# RGBledMiniStick.net
KiCad netlist of a schematic drawn in EAGLE
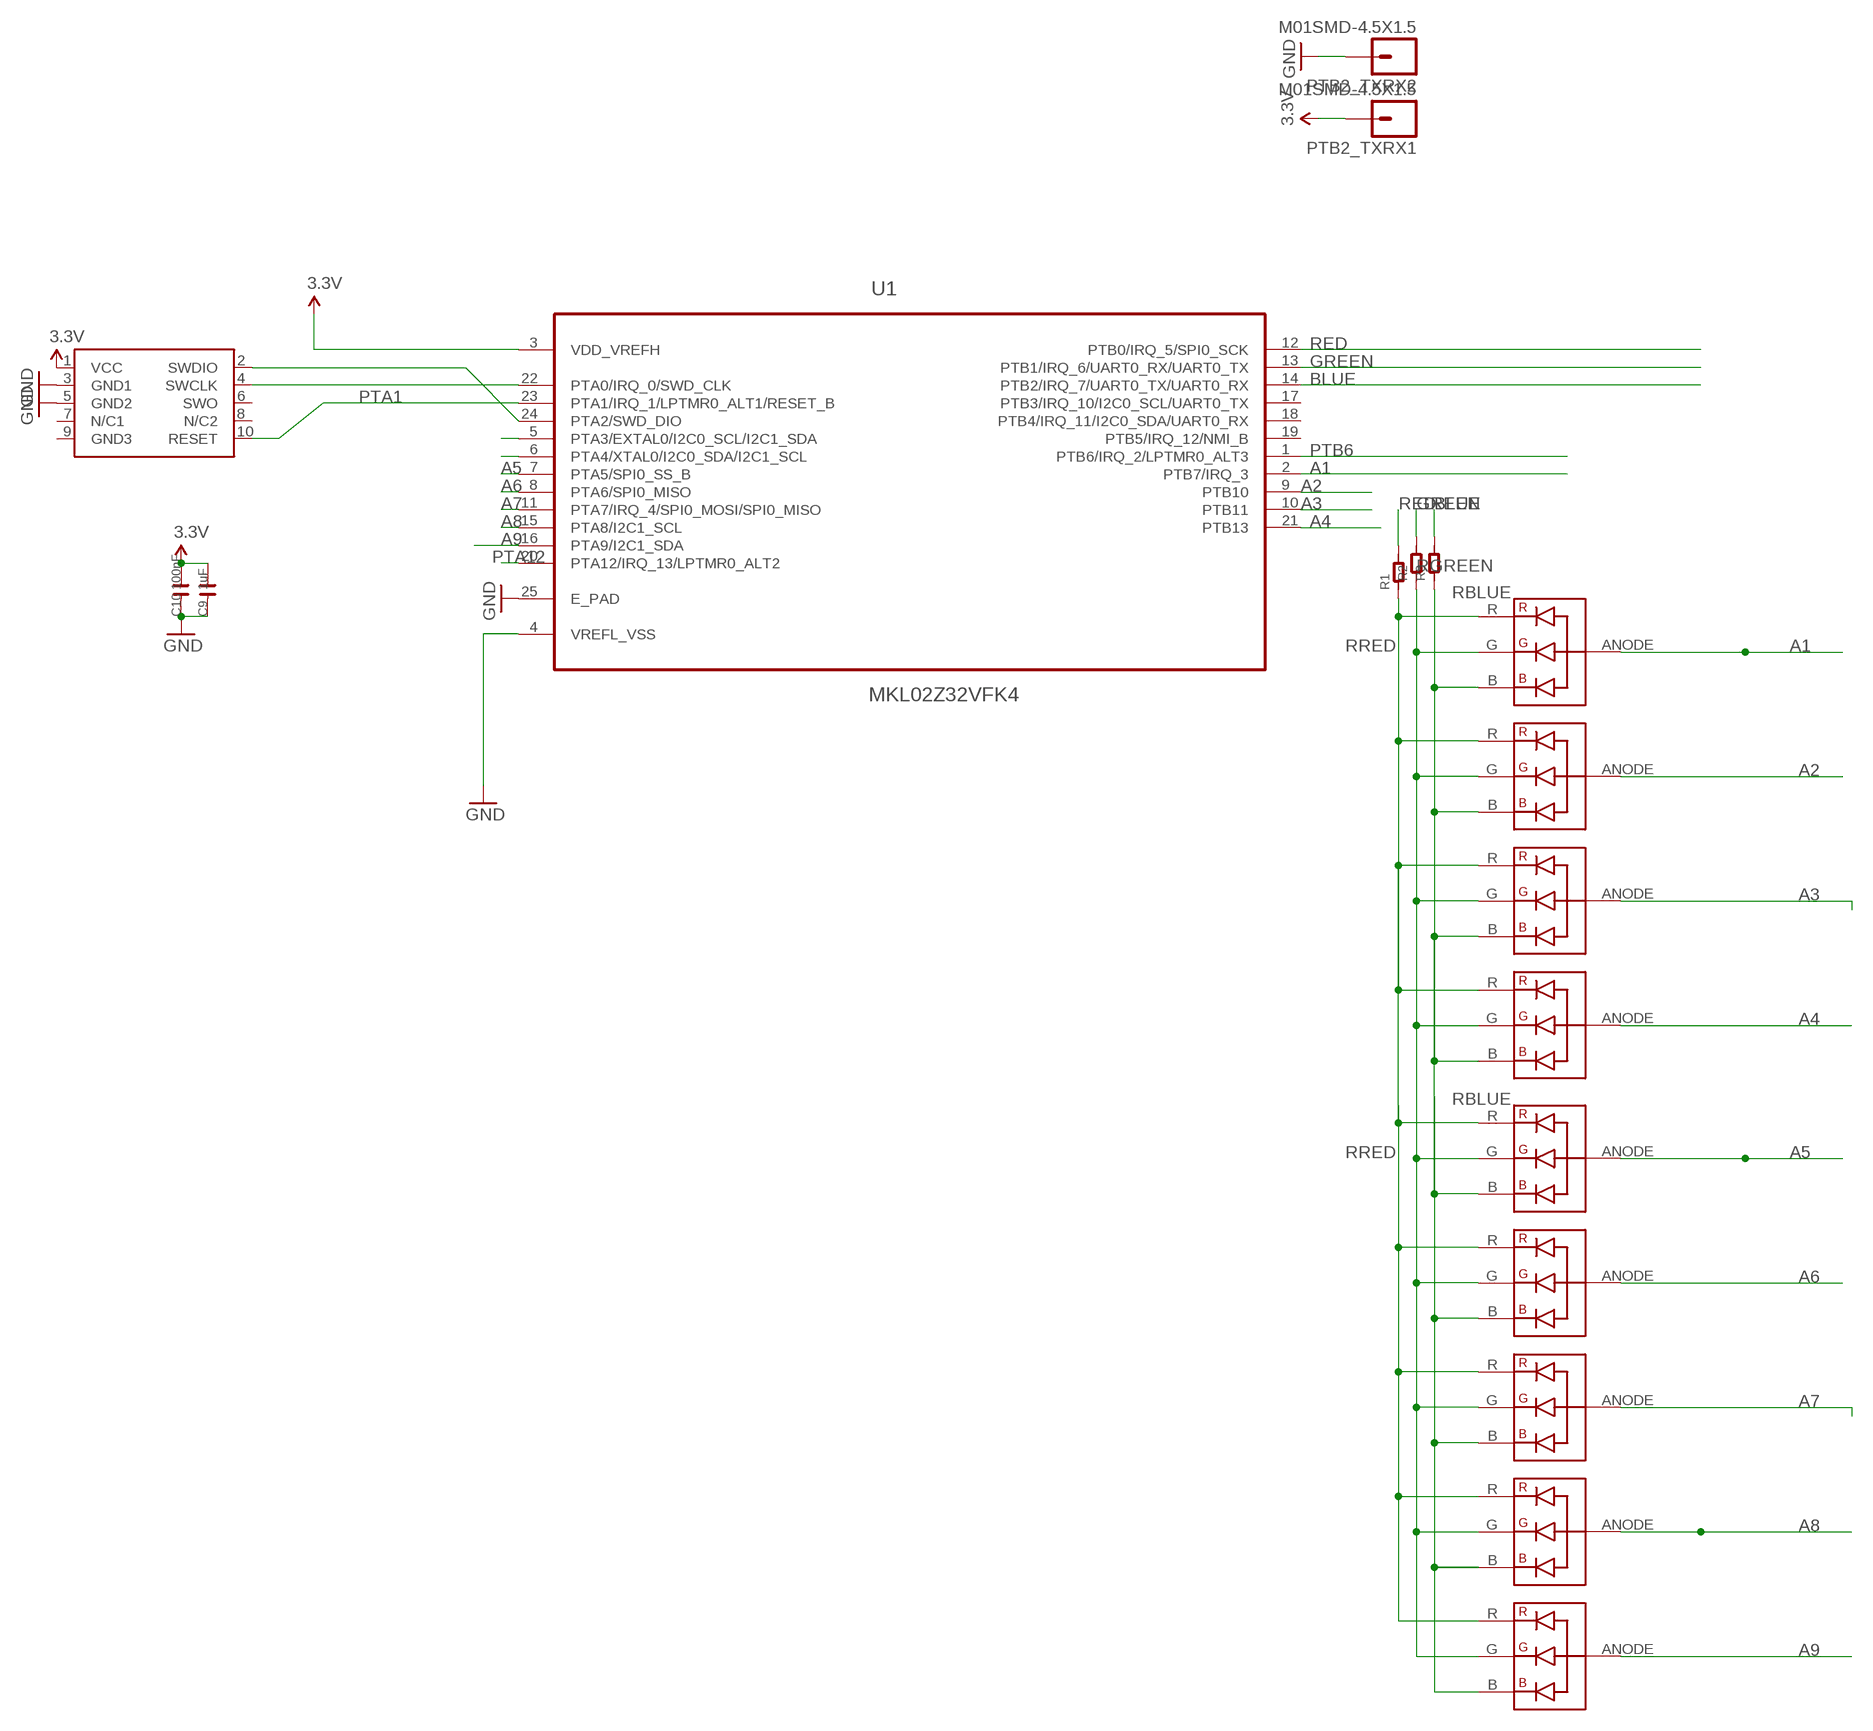
[diagram p0: schematic, sheet 1]

(export (version "E")
  (design (tool "Eeschema 10.0.6"))
  (components
    (comp (ref "C9")
      (value "1uF")
      (footprint "eagle-import:C0603")
      (libsource (lib "eagle-import") (part "C-0603"))
    )
    (comp (ref "C10")
      (value "100nF")
      (footprint "eagle-import:C0603")
      (libsource (lib "eagle-import") (part "C-0603"))
    )
    (comp (ref "PTB2_TXRX1")
      (value "M01SMD-4.5X1.5")
      (footprint "eagle-import:PAD-1.5X4.5")
      (libsource (lib "eagle-import") (part "M01SMD-4.5X1.5"))
    )
    (comp (ref "PTB2_TXRX2")
      (value "M01SMD-4.5X1.5")
      (footprint "eagle-import:PAD-1.5X4.5")
      (libsource (lib "eagle-import") (part "M01SMD-4.5X1.5"))
    )
    (comp (ref "R1")
      (value "R-0603")
      (footprint "eagle-import:R0603")
      (libsource (lib "eagle-import") (part "R-0603"))
    )
    (comp (ref "R2")
      (value "R-0603")
      (footprint "eagle-import:R0603")
      (libsource (lib "eagle-import") (part "R-0603"))
    )
    (comp (ref "R3")
      (value "R-0603")
      (footprint "eagle-import:R0603")
      (libsource (lib "eagle-import") (part "R-0603"))
    )
    (comp (ref "SWD1")
      (value "CORTEX_SWD")
      (footprint "eagle-import:M50-3600542")
      (libsource (lib "eagle-import") (part "CORTEX_SWD"))
    )
    (comp (ref "U$1")
      (value "RGBLED_COMMONANODE")
      (footprint "eagle-import:3.5X2.8_RGB_LED")
      (libsource (lib "eagle-import") (part "RGBLED_COMMONANODE"))
    )
    (comp (ref "U$2")
      (value "RGBLED_COMMONANODE")
      (footprint "eagle-import:3.5X2.8_RGB_LED")
      (libsource (lib "eagle-import") (part "RGBLED_COMMONANODE"))
    )
    (comp (ref "U$3")
      (value "RGBLED_COMMONANODE")
      (footprint "eagle-import:3.5X2.8_RGB_LED")
      (libsource (lib "eagle-import") (part "RGBLED_COMMONANODE"))
    )
    (comp (ref "U$4")
      (value "RGBLED_COMMONANODE")
      (footprint "eagle-import:3.5X2.8_RGB_LED")
      (libsource (lib "eagle-import") (part "RGBLED_COMMONANODE"))
    )
    (comp (ref "U$5")
      (value "RGBLED_COMMONANODE")
      (footprint "eagle-import:3.5X2.8_RGB_LED")
      (libsource (lib "eagle-import") (part "RGBLED_COMMONANODE"))
    )
    (comp (ref "U$6")
      (value "RGBLED_COMMONANODE")
      (footprint "eagle-import:3.5X2.8_RGB_LED")
      (libsource (lib "eagle-import") (part "RGBLED_COMMONANODE"))
    )
    (comp (ref "U$7")
      (value "RGBLED_COMMONANODE")
      (footprint "eagle-import:3.5X2.8_RGB_LED")
      (libsource (lib "eagle-import") (part "RGBLED_COMMONANODE"))
    )
    (comp (ref "U$8")
      (value "RGBLED_COMMONANODE")
      (footprint "eagle-import:3.5X2.8_RGB_LED")
      (libsource (lib "eagle-import") (part "RGBLED_COMMONANODE"))
    )
    (comp (ref "U$9")
      (value "RGBLED_COMMONANODE")
      (footprint "eagle-import:3.5X2.8_RGB_LED")
      (libsource (lib "eagle-import") (part "RGBLED_COMMONANODE"))
    )
    (comp (ref "U1")
      (value "MKL02Z32VFK4")
      (footprint "eagle-import:QFN50P400X400X100-25N")
      (libsource (lib "eagle-import") (part "MKL02Z32VFK4"))
    )
  )
  (nets
    (net (code "1") (name "/A1") (class "Default")
      (node (ref "U$1") (pin "ANODE") (pinfunction "ANODE_ANODE") (pintype "bidirectional"))
      (node (ref "U1") (pin "2") (pinfunction "PTB7/IRQ_3_2") (pintype "bidirectional"))
    )
    (net (code "2") (name "/A2") (class "Default")
      (node (ref "U$2") (pin "ANODE") (pinfunction "ANODE_ANODE") (pintype "bidirectional"))
      (node (ref "U1") (pin "9") (pinfunction "PTB10_9") (pintype "bidirectional"))
    )
    (net (code "3") (name "/A3") (class "Default")
      (node (ref "U$3") (pin "ANODE") (pinfunction "ANODE_ANODE") (pintype "bidirectional"))
      (node (ref "U1") (pin "10") (pinfunction "PTB11_10") (pintype "bidirectional"))
    )
    (net (code "4") (name "/A4") (class "Default")
      (node (ref "U$4") (pin "ANODE") (pinfunction "ANODE_ANODE") (pintype "bidirectional"))
      (node (ref "U1") (pin "21") (pinfunction "PTB13_21") (pintype "bidirectional"))
    )
    (net (code "5") (name "/A5") (class "Default")
      (node (ref "U$5") (pin "ANODE") (pinfunction "ANODE_ANODE") (pintype "bidirectional"))
      (node (ref "U1") (pin "7") (pinfunction "PTA5/SPI0_SS_B_7") (pintype "bidirectional"))
    )
    (net (code "6") (name "/A6") (class "Default")
      (node (ref "U$6") (pin "ANODE") (pinfunction "ANODE_ANODE") (pintype "bidirectional"))
      (node (ref "U1") (pin "8") (pinfunction "PTA6/SPI0_MISO_8") (pintype "bidirectional"))
    )
    (net (code "7") (name "/A7") (class "Default")
      (node (ref "U$7") (pin "ANODE") (pinfunction "ANODE_ANODE") (pintype "bidirectional"))
      (node (ref "U1") (pin "11") (pinfunction "PTA7/IRQ_4/SPI0_MOSI/SPI0_MISO_11") (pintype "bidirectional"))
    )
    (net (code "8") (name "/A8") (class "Default")
      (node (ref "U$8") (pin "ANODE") (pinfunction "ANODE_ANODE") (pintype "bidirectional"))
      (node (ref "U1") (pin "15") (pinfunction "PTA8/I2C1_SCL_15") (pintype "bidirectional"))
    )
    (net (code "9") (name "/A9") (class "Default")
      (node (ref "U$9") (pin "ANODE") (pinfunction "ANODE_ANODE") (pintype "bidirectional"))
      (node (ref "U1") (pin "16") (pinfunction "PTA9/I2C1_SDA_16") (pintype "bidirectional"))
    )
    (net (code "10") (name "/BLUE") (class "Default")
      (node (ref "R3") (pin "2") (pinfunction "2_2") (pintype "bidirectional"))
      (node (ref "U1") (pin "14") (pinfunction "PTB2/IRQ_7/UART0_TX/UART0_RX_14") (pintype "bidirectional"))
    )
    (net (code "11") (name "/GREEN") (class "Default")
      (node (ref "R2") (pin "2") (pinfunction "2_2") (pintype "bidirectional"))
      (node (ref "U1") (pin "13") (pinfunction "PTB1/IRQ_6/UART0_RX/UART0_TX_13") (pintype "bidirectional"))
    )
    (net (code "12") (name "/PTA1") (class "Default")
      (node (ref "SWD1") (pin "10") (pinfunction "RESET_10") (pintype "bidirectional"))
      (node (ref "U1") (pin "23") (pinfunction "PTA1/IRQ_1/LPTMR0_ALT1/RESET_B_23") (pintype "bidirectional"))
    )
    (net (code "13") (name "/PTA12") (class "Default")
      (node (ref "U1") (pin "20") (pinfunction "PTA12/IRQ_13/LPTMR0_ALT2_20") (pintype "bidirectional"))
    )
    (net (code "14") (name "/PTB6") (class "Default")
      (node (ref "U1") (pin "1") (pinfunction "PTB6/IRQ_2/LPTMR0_ALT3_1") (pintype "bidirectional"))
    )
    (net (code "15") (name "/RBLUE") (class "Default")
      (node (ref "R3") (pin "1") (pinfunction "1_1") (pintype "bidirectional"))
      (node (ref "U$1") (pin "B") (pinfunction "B_B") (pintype "bidirectional"))
      (node (ref "U$2") (pin "B") (pinfunction "B_B") (pintype "bidirectional"))
      (node (ref "U$3") (pin "B") (pinfunction "B_B") (pintype "bidirectional"))
      (node (ref "U$4") (pin "B") (pinfunction "B_B") (pintype "bidirectional"))
      (node (ref "U$5") (pin "B") (pinfunction "B_B") (pintype "bidirectional"))
      (node (ref "U$6") (pin "B") (pinfunction "B_B") (pintype "bidirectional"))
      (node (ref "U$7") (pin "B") (pinfunction "B_B") (pintype "bidirectional"))
      (node (ref "U$8") (pin "B") (pinfunction "B_B") (pintype "bidirectional"))
      (node (ref "U$9") (pin "B") (pinfunction "B_B") (pintype "bidirectional"))
    )
    (net (code "16") (name "/RED") (class "Default")
      (node (ref "R1") (pin "2") (pinfunction "2_2") (pintype "bidirectional"))
      (node (ref "U1") (pin "12") (pinfunction "PTB0/IRQ_5/SPI0_SCK_12") (pintype "bidirectional"))
    )
    (net (code "17") (name "/RGREEN") (class "Default")
      (node (ref "R2") (pin "1") (pinfunction "1_1") (pintype "bidirectional"))
      (node (ref "U$1") (pin "G") (pinfunction "G_G") (pintype "bidirectional"))
      (node (ref "U$2") (pin "G") (pinfunction "G_G") (pintype "bidirectional"))
      (node (ref "U$3") (pin "G") (pinfunction "G_G") (pintype "bidirectional"))
      (node (ref "U$4") (pin "G") (pinfunction "G_G") (pintype "bidirectional"))
      (node (ref "U$5") (pin "G") (pinfunction "G_G") (pintype "bidirectional"))
      (node (ref "U$6") (pin "G") (pinfunction "G_G") (pintype "bidirectional"))
      (node (ref "U$7") (pin "G") (pinfunction "G_G") (pintype "bidirectional"))
      (node (ref "U$8") (pin "G") (pinfunction "G_G") (pintype "bidirectional"))
      (node (ref "U$9") (pin "G") (pinfunction "G_G") (pintype "bidirectional"))
    )
    (net (code "18") (name "/RRED") (class "Default")
      (node (ref "R1") (pin "1") (pinfunction "1_1") (pintype "bidirectional"))
      (node (ref "U$1") (pin "R") (pinfunction "R_R") (pintype "bidirectional"))
      (node (ref "U$2") (pin "R") (pinfunction "R_R") (pintype "bidirectional"))
      (node (ref "U$3") (pin "R") (pinfunction "R_R") (pintype "bidirectional"))
      (node (ref "U$4") (pin "R") (pinfunction "R_R") (pintype "bidirectional"))
      (node (ref "U$5") (pin "R") (pinfunction "R_R") (pintype "bidirectional"))
      (node (ref "U$6") (pin "R") (pinfunction "R_R") (pintype "bidirectional"))
      (node (ref "U$7") (pin "R") (pinfunction "R_R") (pintype "bidirectional"))
      (node (ref "U$8") (pin "R") (pinfunction "R_R") (pintype "bidirectional"))
      (node (ref "U$9") (pin "R") (pinfunction "R_R") (pintype "bidirectional"))
    )
    (net (code "19") (name "3.3V") (class "Default")
      (node (ref "C10") (pin "2") (pinfunction "2_2") (pintype "bidirectional"))
      (node (ref "C9") (pin "2") (pinfunction "2_2") (pintype "bidirectional"))
      (node (ref "PTB2_TXRX1") (pin "P$1") (pinfunction "1_P$1") (pintype "passive"))
      (node (ref "SWD1") (pin "1") (pinfunction "VCC_1") (pintype "bidirectional"))
      (node (ref "U1") (pin "3") (pinfunction "VDD_VREFH_3") (pintype "power_in"))
    )
    (net (code "20") (name "GND") (class "Default")
      (node (ref "C10") (pin "1") (pinfunction "1_1") (pintype "bidirectional"))
      (node (ref "C9") (pin "1") (pinfunction "1_1") (pintype "bidirectional"))
      (node (ref "PTB2_TXRX2") (pin "P$1") (pinfunction "1_P$1") (pintype "passive"))
      (node (ref "SWD1") (pin "3") (pinfunction "GND1_3") (pintype "bidirectional"))
      (node (ref "SWD1") (pin "5") (pinfunction "GND2_5") (pintype "bidirectional"))
      (node (ref "U1") (pin "25") (pinfunction "E_PAD_25") (pintype "passive"))
      (node (ref "U1") (pin "4") (pinfunction "VREFL_VSS_4") (pintype "passive"))
    )
    (net (code "21") (name "Net-(SWD1-SWCLK)") (class "Default")
      (node (ref "SWD1") (pin "4") (pinfunction "SWCLK_4") (pintype "bidirectional"))
      (node (ref "U1") (pin "22") (pinfunction "PTA0/IRQ_0/SWD_CLK_22") (pintype "bidirectional"))
    )
    (net (code "22") (name "Net-(SWD1-SWDIO)") (class "Default")
      (node (ref "SWD1") (pin "2") (pinfunction "SWDIO_2") (pintype "bidirectional"))
      (node (ref "U1") (pin "24") (pinfunction "PTA2/SWD_DIO_24") (pintype "bidirectional"))
    )
    (net (code "23") (name "unconnected-(SWD1-GND3-Pad9)") (class "Default")
      (node (ref "SWD1") (pin "9") (pinfunction "GND3_9") (pintype "bidirectional"))
    )
    (net (code "24") (name "unconnected-(SWD1-N{slash}C1-Pad7)") (class "Default")
      (node (ref "SWD1") (pin "7") (pinfunction "N/C1_7") (pintype "bidirectional"))
    )
    (net (code "25") (name "unconnected-(SWD1-N{slash}C2-Pad8)") (class "Default")
      (node (ref "SWD1") (pin "8") (pinfunction "N/C2_8") (pintype "bidirectional"))
    )
    (net (code "26") (name "unconnected-(SWD1-SWO-Pad6)") (class "Default")
      (node (ref "SWD1") (pin "6") (pinfunction "SWO_6") (pintype "bidirectional"))
    )
    (net (code "27") (name "unconnected-(U1-PTA3{slash}EXTAL0{slash}I2C0_SCL{slash}I2C1_SDA-Pad5)") (class "Default")
      (node (ref "U1") (pin "5") (pinfunction "PTA3/EXTAL0/I2C0_SCL/I2C1_SDA_5") (pintype "bidirectional"))
    )
    (net (code "28") (name "unconnected-(U1-PTA4{slash}XTAL0{slash}I2C0_SDA{slash}I2C1_SCL-Pad6)") (class "Default")
      (node (ref "U1") (pin "6") (pinfunction "PTA4/XTAL0/I2C0_SDA/I2C1_SCL_6") (pintype "bidirectional"))
    )
    (net (code "29") (name "unconnected-(U1-PTB3{slash}IRQ_10{slash}I2C0_SCL{slash}UART0_TX-Pad17)") (class "Default")
      (node (ref "U1") (pin "17") (pinfunction "PTB3/IRQ_10/I2C0_SCL/UART0_TX_17") (pintype "bidirectional"))
    )
    (net (code "30") (name "unconnected-(U1-PTB4{slash}IRQ_11{slash}I2C0_SDA{slash}UART0_RX-Pad18)") (class "Default")
      (node (ref "U1") (pin "18") (pinfunction "PTB4/IRQ_11/I2C0_SDA/UART0_RX_18") (pintype "bidirectional"))
    )
    (net (code "31") (name "unconnected-(U1-PTB5{slash}IRQ_12{slash}NMI_B-Pad19)") (class "Default")
      (node (ref "U1") (pin "19") (pinfunction "PTB5/IRQ_12/NMI_B_19") (pintype "bidirectional"))
    )
  )
)
